# AFE_ADS129X.net
KiCad netlist of a schematic drawn in Altium Designer
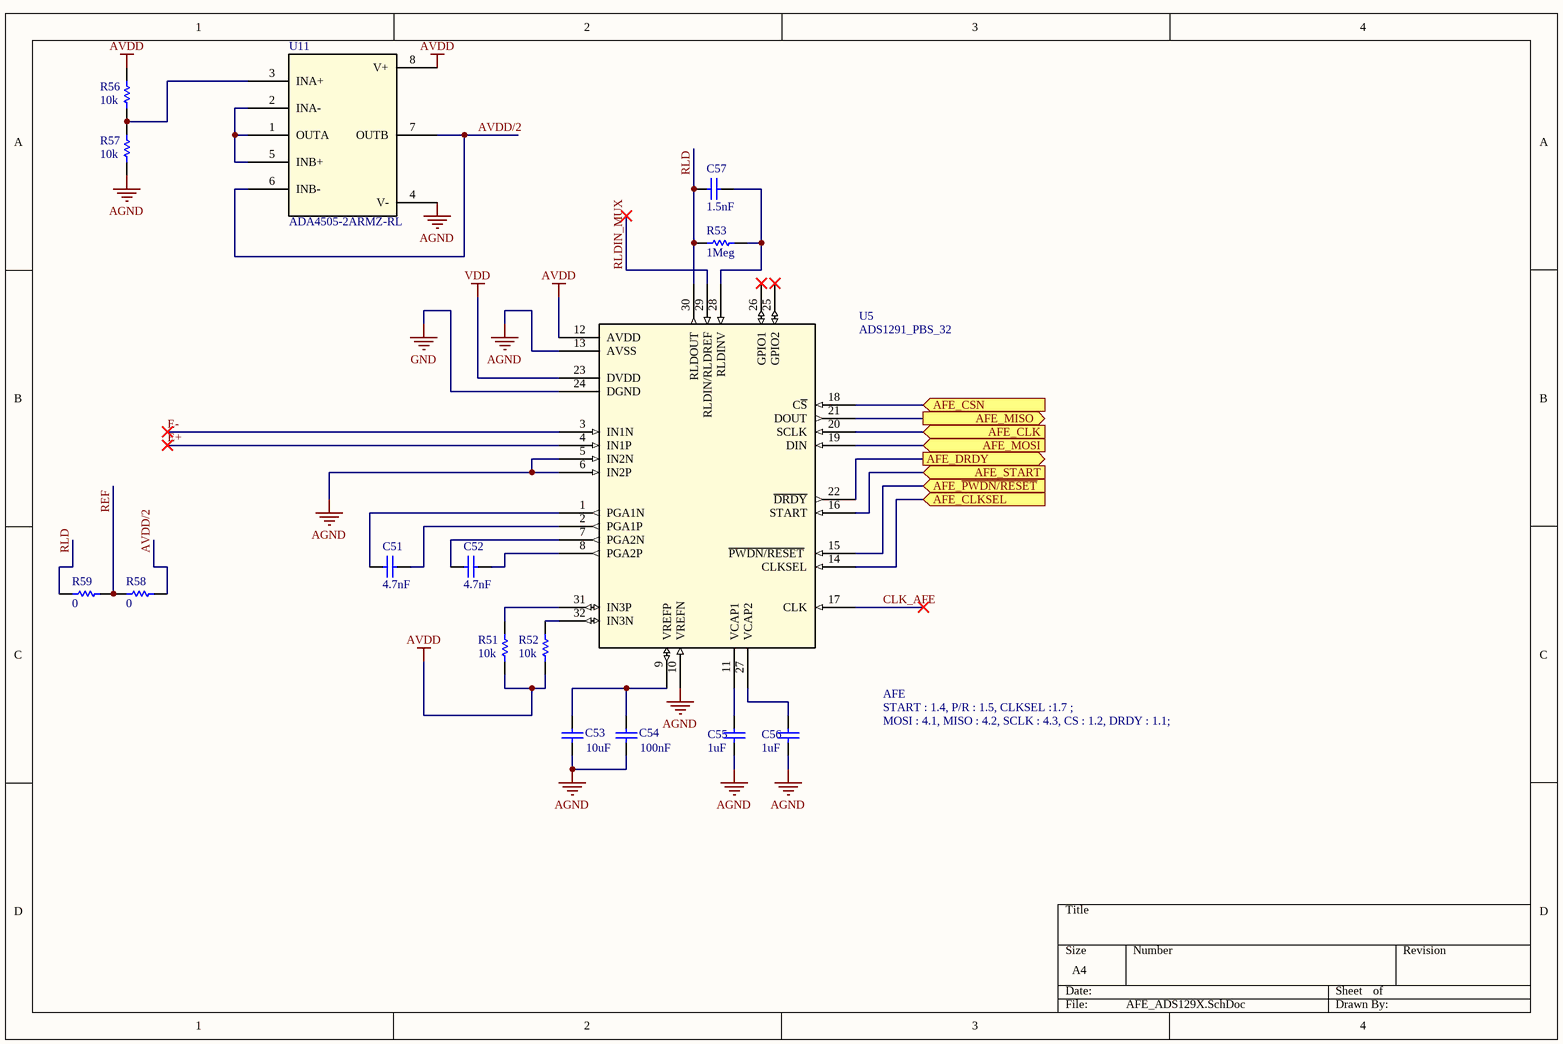
[diagram p0: AFE_ADS129X.SchDoc]

(export (version "E")
  (design (tool "Eeschema 10.0.6"))
  (components
    (comp (ref "C51")
      (value "4.7nF")
      (footprint "0402")
      (description "Capacitor (Semiconductor SIM Model)")
      (fields (field (name "Comment") "Cap Semi") (field (name "PUBLISHER") "Altium Limited"))
      (libsource (lib "Miscellaneous Devices") (part "Cap Semi"))
    )
    (comp (ref "C52")
      (value "4.7nF")
      (footprint "0402")
      (description "Capacitor (Semiconductor SIM Model)")
      (fields (field (name "Comment") "Cap Semi") (field (name "PUBLISHER") "Altium Limited"))
      (libsource (lib "Miscellaneous Devices") (part "Cap Semi"))
    )
    (comp (ref "C53")
      (value "10uF")
      (footprint "0402")
      (description "Capacitor (Semiconductor SIM Model)")
      (fields (field (name "Comment") "Cap Semi") (field (name "PUBLISHER") "Altium Limited"))
      (libsource (lib "Miscellaneous Devices") (part "Cap Semi"))
    )
    (comp (ref "C54")
      (value "100nF")
      (footprint "0402")
      (description "Capacitor (Semiconductor SIM Model)")
      (fields (field (name "Comment") "Cap Semi") (field (name "PUBLISHER") "Altium Limited"))
      (libsource (lib "Miscellaneous Devices") (part "Cap Semi"))
    )
    (comp (ref "C55")
      (value "1uF")
      (footprint "0402")
      (description "Capacitor (Semiconductor SIM Model)")
      (fields (field (name "Comment") "Cap Semi") (field (name "PUBLISHER") "Altium Limited"))
      (libsource (lib "Miscellaneous Devices") (part "Cap Semi"))
    )
    (comp (ref "C56")
      (value "1uF")
      (footprint "0402")
      (description "Capacitor (Semiconductor SIM Model)")
      (fields (field (name "Comment") "Cap Semi") (field (name "PUBLISHER") "Altium Limited"))
      (libsource (lib "Miscellaneous Devices") (part "Cap Semi"))
    )
    (comp (ref "C57")
      (value "1.5nF")
      (footprint "0402")
      (description "Capacitor (Semiconductor SIM Model)")
      (fields (field (name "Comment") "Cap Semi") (field (name "PUBLISHER") "Altium Limited"))
      (libsource (lib "Miscellaneous Devices") (part "Cap Semi"))
    )
    (comp (ref "R51")
      (value "10k")
      (footprint "0402")
      (description "Semiconductor Resistor")
      (fields (field (name "PUBLISHER") "Altium Limited"))
      (libsource (lib "Miscellaneous Devices") (part "Res Semi"))
    )
    (comp (ref "R52")
      (value "10k")
      (footprint "0402")
      (description "Semiconductor Resistor")
      (fields (field (name "PUBLISHER") "Altium Limited"))
      (libsource (lib "Miscellaneous Devices") (part "Res Semi"))
    )
    (comp (ref "R53")
      (value "1Meg")
      (footprint "0402")
      (description "Semiconductor Resistor")
      (fields (field (name "PUBLISHER") "Altium Limited"))
      (libsource (lib "Miscellaneous Devices") (part "Res Semi"))
    )
    (comp (ref "R56")
      (value "10k")
      (footprint "0402")
      (description "Semiconductor Resistor")
      (fields (field (name "PUBLISHER") "Altium Limited"))
      (libsource (lib "Miscellaneous Devices") (part "Res Semi"))
    )
    (comp (ref "R57")
      (value "10k")
      (footprint "0402")
      (description "Semiconductor Resistor")
      (fields (field (name "PUBLISHER") "Altium Limited"))
      (libsource (lib "Miscellaneous Devices") (part "Res Semi"))
    )
    (comp (ref "R58")
      (value "0")
      (footprint "0402")
      (description "Semiconductor Resistor")
      (fields (field (name "PUBLISHER") "Altium Limited"))
      (libsource (lib "Miscellaneous Devices") (part "Res Semi"))
    )
    (comp (ref "R59")
      (value "0")
      (footprint "0402")
      (description "Semiconductor Resistor")
      (fields (field (name "PUBLISHER") "Altium Limited"))
      (libsource (lib "Miscellaneous Devices") (part "Res Semi"))
    )
    (comp (ref "U5")
      (value "ADS1291_PBS_32")
      (footprint "ADS129X")
      (description "Imported")
      (fields
        (field (name "MANUFACTURER") "Texas Instruments")
        (field (name "GENERIC_PART_NUMBER") "ADS1291")
      )
      (libsource (lib "ADS129X") (part "ADS1291_PBS_32"))
    )
    (comp (ref "U11")
      (value "ADA4505-2ARMZ-RL")
      (footprint "ADA4505-2ARM")
      (description "Imported")
      (libsource (lib "ADA405-2ARM") (part "ADA4505-2ARMZ-RL"))
    )
  )
  (nets
    (net (code "1") (name "/AFE_CLK") (class "Default")
      (node (ref "U5") (pin "20") (pinfunction "SCLK_20") (pintype "input"))
    )
    (net (code "2") (name "/AFE_CLKSEL") (class "Default")
      (node (ref "U5") (pin "14") (pinfunction "CLKSEL_14") (pintype "input"))
    )
    (net (code "3") (name "/AFE_CSN") (class "Default")
      (node (ref "U5") (pin "18") (pinfunction "C~{S}_18") (pintype "input"))
    )
    (net (code "4") (name "/AFE_DRDY") (class "Default")
      (node (ref "U5") (pin "22") (pinfunction "~{DRDY}_22") (pintype "output"))
    )
    (net (code "5") (name "/AFE_MISO") (class "Default")
      (node (ref "U5") (pin "21") (pinfunction "DOUT_21") (pintype "output"))
    )
    (net (code "6") (name "/AFE_MOSI") (class "Default")
      (node (ref "U5") (pin "19") (pinfunction "DIN_19") (pintype "input"))
    )
    (net (code "7") (name "/AFE_START") (class "Default")
      (node (ref "U5") (pin "16") (pinfunction "START_16") (pintype "input"))
    )
    (net (code "8") (name "/AFE_~{PWDN{slash}RESET}") (class "Default")
      (node (ref "U5") (pin "15") (pinfunction "~{PWDN/RESET}_15") (pintype "input"))
    )
    (net (code "9") (name "/AVDD{slash}2") (class "Default")
      (node (ref "R58") (pin "1") (pinfunction "1_1") (pintype "passive"))
      (node (ref "U11") (pin "6") (pinfunction "INB-_6") (pintype "passive"))
      (node (ref "U11") (pin "7") (pinfunction "OUTB_7") (pintype "passive"))
    )
    (net (code "10") (name "/CLK_AFE") (class "Default")
      (node (ref "U5") (pin "17") (pinfunction "CLK_17") (pintype "input+no_connect"))
    )
    (net (code "11") (name "/E+") (class "Default")
      (node (ref "U5") (pin "4") (pinfunction "IN1P_4") (pintype "input+no_connect"))
    )
    (net (code "12") (name "/E-") (class "Default")
      (node (ref "U5") (pin "3") (pinfunction "IN1N_3") (pintype "input+no_connect"))
    )
    (net (code "13") (name "/REF") (class "Default")
      (node (ref "R58") (pin "2") (pinfunction "2_2") (pintype "passive"))
      (node (ref "R59") (pin "1") (pinfunction "1_1") (pintype "passive"))
    )
    (net (code "14") (name "/RLD") (class "Default")
      (node (ref "C57") (pin "2") (pinfunction "2_2") (pintype "passive"))
      (node (ref "R53") (pin "2") (pinfunction "2_2") (pintype "passive"))
      (node (ref "R59") (pin "2") (pinfunction "2_2") (pintype "passive"))
      (node (ref "U5") (pin "30") (pinfunction "RLDOUT_30") (pintype "output"))
    )
    (net (code "15") (name "/RLDIN_MUX") (class "Default")
      (node (ref "U5") (pin "29") (pinfunction "RLDIN/RLDREF_29") (pintype "input+no_connect"))
    )
    (net (code "16") (name "AGND") (class "Default")
      (node (ref "C53") (pin "2") (pinfunction "2_2") (pintype "passive"))
      (node (ref "C54") (pin "2") (pinfunction "2_2") (pintype "passive"))
      (node (ref "C55") (pin "2") (pinfunction "2_2") (pintype "passive"))
      (node (ref "C56") (pin "2") (pinfunction "2_2") (pintype "passive"))
      (node (ref "R57") (pin "1") (pinfunction "1_1") (pintype "passive"))
      (node (ref "U11") (pin "4") (pinfunction "V-_4") (pintype "power_in"))
      (node (ref "U5") (pin "10") (pinfunction "VREFN_10") (pintype "input"))
      (node (ref "U5") (pin "13") (pinfunction "AVSS_13") (pintype "power_in"))
      (node (ref "U5") (pin "5") (pinfunction "IN2N_5") (pintype "input"))
      (node (ref "U5") (pin "6") (pinfunction "IN2P_6") (pintype "input"))
    )
    (net (code "17") (name "AVDD") (class "Default")
      (node (ref "R51") (pin "1") (pinfunction "1_1") (pintype "passive"))
      (node (ref "R52") (pin "1") (pinfunction "1_1") (pintype "passive"))
      (node (ref "R56") (pin "2") (pinfunction "2_2") (pintype "passive"))
      (node (ref "U11") (pin "8") (pinfunction "V+_8") (pintype "power_in"))
      (node (ref "U5") (pin "12") (pinfunction "AVDD_12") (pintype "power_in"))
    )
    (net (code "18") (name "GND") (class "Default")
      (node (ref "U5") (pin "24") (pinfunction "DGND_24") (pintype "power_in"))
    )
    (net (code "19") (name "Net-(U5-IN3N)") (class "Default")
      (node (ref "R52") (pin "2") (pinfunction "2_2") (pintype "passive"))
      (node (ref "U5") (pin "32") (pinfunction "IN3N_32") (pintype "bidirectional"))
    )
    (net (code "20") (name "Net-(U5-IN3P)") (class "Default")
      (node (ref "R51") (pin "2") (pinfunction "2_2") (pintype "passive"))
      (node (ref "U5") (pin "31") (pinfunction "IN3P_31") (pintype "bidirectional"))
    )
    (net (code "21") (name "Net-(U5-PGA1N)") (class "Default")
      (node (ref "C51") (pin "1") (pinfunction "1_1") (pintype "passive"))
      (node (ref "U5") (pin "1") (pinfunction "PGA1N_1") (pintype "output"))
    )
    (net (code "22") (name "Net-(U5-PGA1P)") (class "Default")
      (node (ref "C51") (pin "2") (pinfunction "2_2") (pintype "passive"))
      (node (ref "U5") (pin "2") (pinfunction "PGA1P_2") (pintype "output"))
    )
    (net (code "23") (name "Net-(U5-PGA2N)") (class "Default")
      (node (ref "C52") (pin "1") (pinfunction "1_1") (pintype "passive"))
      (node (ref "U5") (pin "7") (pinfunction "PGA2N_7") (pintype "output"))
    )
    (net (code "24") (name "Net-(U5-PGA2P)") (class "Default")
      (node (ref "C52") (pin "2") (pinfunction "2_2") (pintype "passive"))
      (node (ref "U5") (pin "8") (pinfunction "PGA2P_8") (pintype "output"))
    )
    (net (code "25") (name "Net-(U5-RLDINV)") (class "Default")
      (node (ref "C57") (pin "1") (pinfunction "1_1") (pintype "passive"))
      (node (ref "R53") (pin "1") (pinfunction "1_1") (pintype "passive"))
      (node (ref "U5") (pin "28") (pinfunction "RLDINV_28") (pintype "input"))
    )
    (net (code "26") (name "Net-(U5-VCAP1)") (class "Default")
      (node (ref "C55") (pin "1") (pinfunction "1_1") (pintype "passive"))
      (node (ref "U5") (pin "11") (pinfunction "VCAP1_11") (pintype "passive"))
    )
    (net (code "27") (name "Net-(U5-VCAP2)") (class "Default")
      (node (ref "C56") (pin "1") (pinfunction "1_1") (pintype "passive"))
      (node (ref "U5") (pin "27") (pinfunction "VCAP2_27") (pintype "passive"))
    )
    (net (code "28") (name "Net-(U5-VREFP)") (class "Default")
      (node (ref "C53") (pin "1") (pinfunction "1_1") (pintype "passive"))
      (node (ref "C54") (pin "1") (pinfunction "1_1") (pintype "passive"))
      (node (ref "U5") (pin "9") (pinfunction "VREFP_9") (pintype "bidirectional"))
    )
    (net (code "29") (name "Net-(U11-INA+)") (class "Default")
      (node (ref "R56") (pin "1") (pinfunction "1_1") (pintype "passive"))
      (node (ref "R57") (pin "2") (pinfunction "2_2") (pintype "passive"))
      (node (ref "U11") (pin "3") (pinfunction "INA+_3") (pintype "passive"))
    )
    (net (code "30") (name "Net-(U11-INA-)") (class "Default")
      (node (ref "U11") (pin "1") (pinfunction "OUTA_1") (pintype "passive"))
      (node (ref "U11") (pin "2") (pinfunction "INA-_2") (pintype "passive"))
      (node (ref "U11") (pin "5") (pinfunction "INB+_5") (pintype "passive"))
    )
    (net (code "31") (name "VDD") (class "Default")
      (node (ref "U5") (pin "23") (pinfunction "DVDD_23") (pintype "power_in"))
    )
    (net (code "32") (name "unconnected-(U5-GPIO1-Pad26)") (class "Default")
      (node (ref "U5") (pin "26") (pinfunction "GPIO1_26") (pintype "bidirectional+no_connect"))
    )
    (net (code "33") (name "unconnected-(U5-GPIO2-Pad25)") (class "Default")
      (node (ref "U5") (pin "25") (pinfunction "GPIO2_25") (pintype "bidirectional+no_connect"))
    )
  )
)
